# Bootselector_SMD.net
KiCad netlist of a schematic drawn in EAGLE
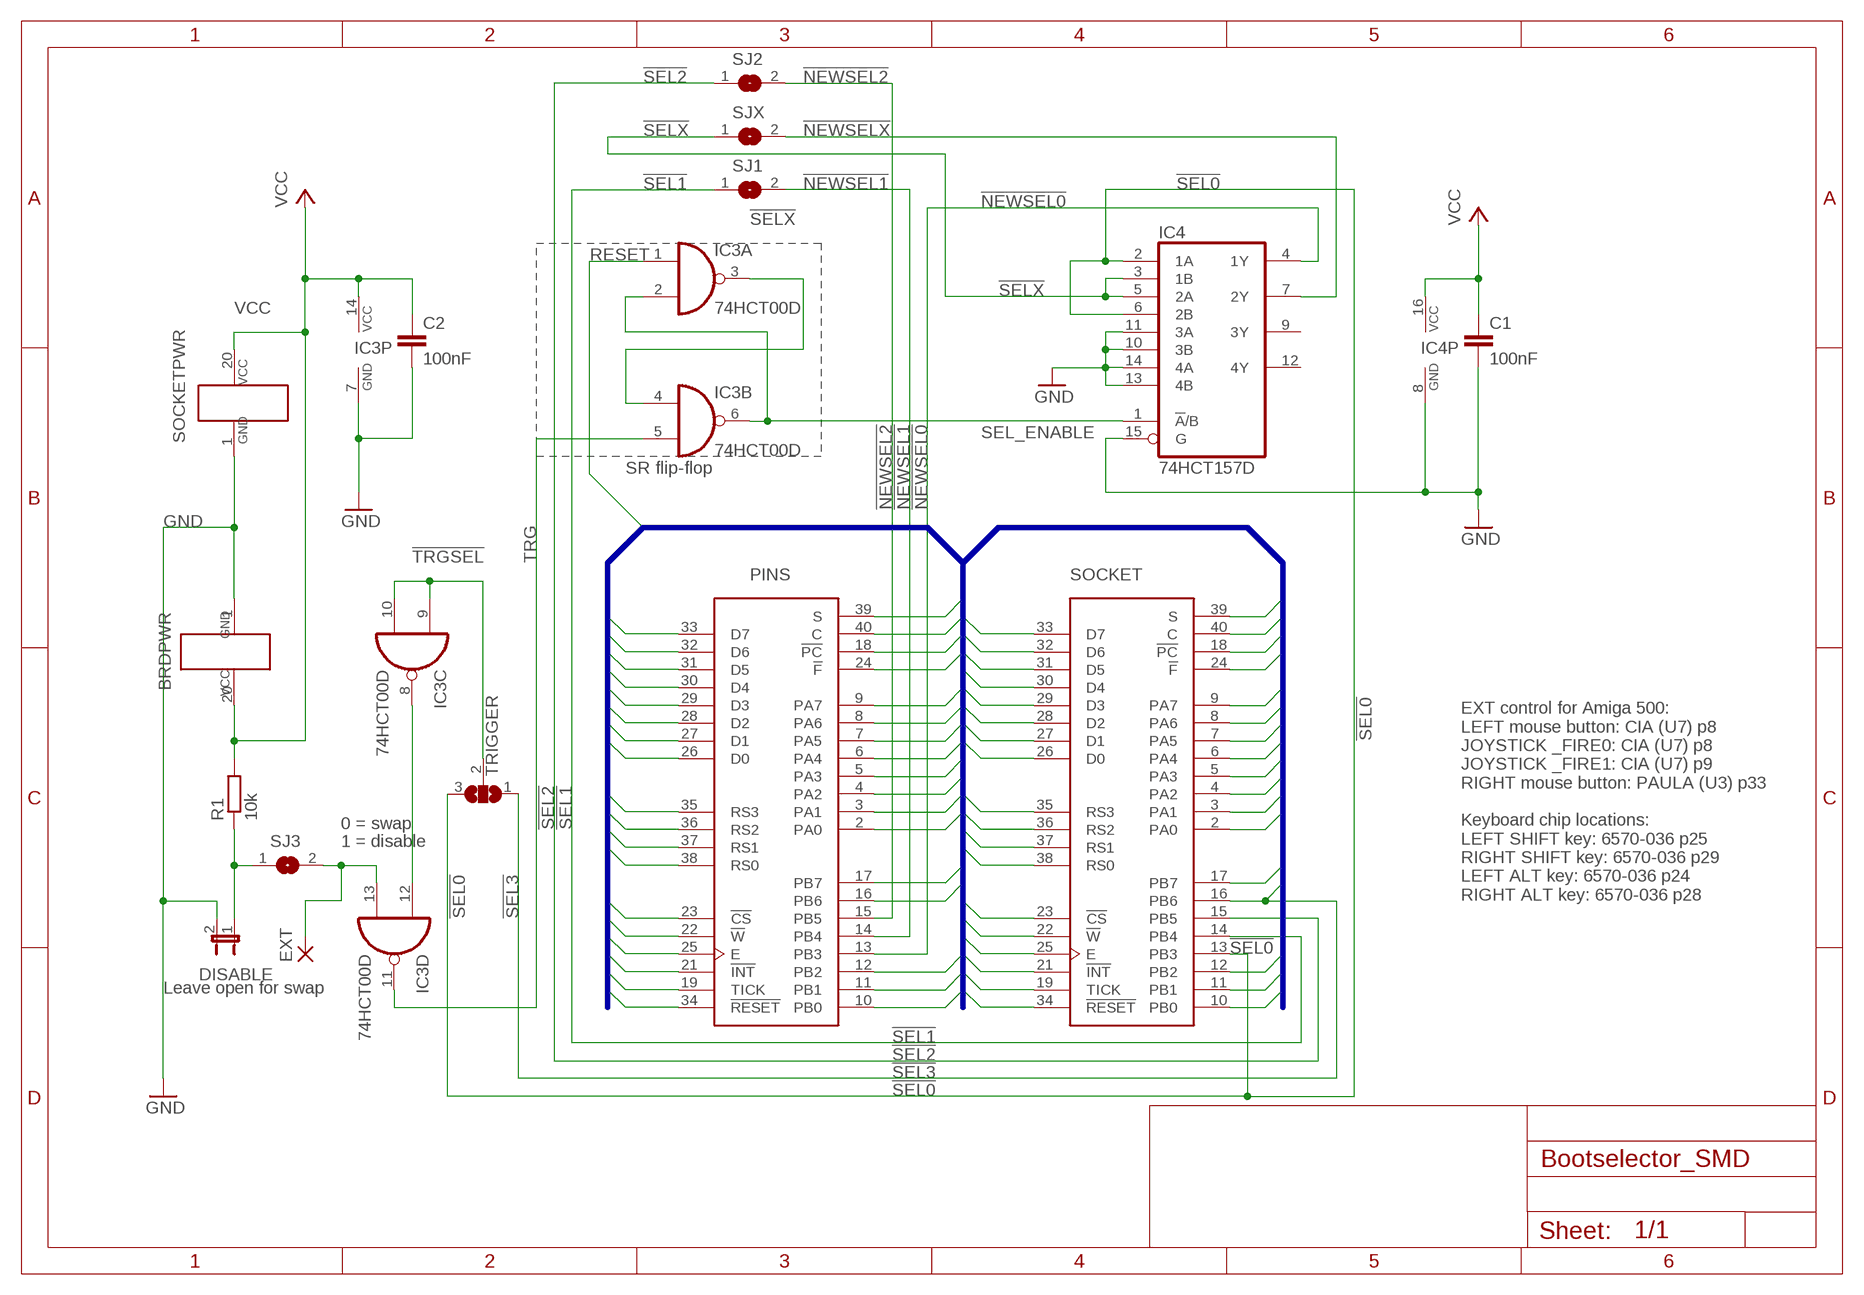
[diagram p0: schematic, sheet 1]

(export (version "E")
  (design (tool "Eeschema 10.0.6"))
  (components
    (comp (ref "BRD")
      (value "PINS")
      (footprint "eagle-import:DIP40-6")
      (libsource (lib "eagle-import") (part "CIA_DIP"))
    )
    (comp (ref "C1")
      (value "100nF")
      (footprint "eagle-import:C0805")
      (libsource (lib "eagle-import") (part "C-EUC0805"))
    )
    (comp (ref "C2")
      (value "100nF")
      (footprint "eagle-import:C0805K")
      (libsource (lib "eagle-import") (part "C-EUC0805K"))
    )
    (comp (ref "DISABLE")
      (value "Leave open for swap")
      (footprint "eagle-import:JP1")
      (libsource (lib "eagle-import") (part "JP1E"))
    )
    (comp (ref "EXT")
      (value "SMD2")
      (footprint "eagle-import:SMD1,27-2,54")
      (libsource (lib "eagle-import") (part "SMD2"))
    )
    (comp (ref "IC3")
      (value "74HCT00D")
      (footprint "eagle-import:SO14")
      (libsource (lib "eagle-import") (part "7400DHCT"))
    )
    (comp (ref "IC4")
      (value "74HCT157D")
      (footprint "eagle-import:SO16")
      (libsource (lib "eagle-import") (part "74157DHCT"))
    )
    (comp (ref "R1")
      (value "10k")
      (footprint "eagle-import:R0805")
      (libsource (lib "eagle-import") (part "R-EU_R0805"))
    )
    (comp (ref "SJ1") (value "SJ") (footprint "eagle-import:SJ") (libsource (lib "eagle-import") (part "SJ")))
    (comp (ref "SJ2") (value "SJ") (footprint "eagle-import:SJ") (libsource (lib "eagle-import") (part "SJ")))
    (comp (ref "SJ3") (value "SJ") (footprint "eagle-import:SJ") (libsource (lib "eagle-import") (part "SJ")))
    (comp (ref "SJX") (value "SJ") (footprint "eagle-import:SJ") (libsource (lib "eagle-import") (part "SJ")))
    (comp (ref "SOCKET")
      (value "CIA_DIP")
      (footprint "eagle-import:DIP40-6")
      (libsource (lib "eagle-import") (part "CIA_DIP"))
    )
    (comp (ref "TRIGGER")
      (value "SJ2W")
      (footprint "eagle-import:SJ_2")
      (libsource (lib "eagle-import") (part "SJ2W"))
    )
  )
  (nets
    (net (code "1") (name "/C") (class "Default")
      (node (ref "BRD") (pin "40") (pinfunction "C_40") (pintype "bidirectional"))
      (node (ref "SOCKET") (pin "40") (pinfunction "C_40") (pintype "bidirectional"))
    )
    (net (code "2") (name "/CS") (class "Default")
      (node (ref "BRD") (pin "23") (pinfunction "~{CS}_23") (pintype "input"))
      (node (ref "SOCKET") (pin "23") (pinfunction "~{CS}_23") (pintype "input"))
    )
    (net (code "3") (name "/D0") (class "Default")
      (node (ref "BRD") (pin "26") (pinfunction "D0_26") (pintype "bidirectional"))
      (node (ref "SOCKET") (pin "26") (pinfunction "D0_26") (pintype "bidirectional"))
    )
    (net (code "4") (name "/D1") (class "Default")
      (node (ref "BRD") (pin "27") (pinfunction "D1_27") (pintype "bidirectional"))
      (node (ref "SOCKET") (pin "27") (pinfunction "D1_27") (pintype "bidirectional"))
    )
    (net (code "5") (name "/D2") (class "Default")
      (node (ref "BRD") (pin "28") (pinfunction "D2_28") (pintype "bidirectional"))
      (node (ref "SOCKET") (pin "28") (pinfunction "D2_28") (pintype "bidirectional"))
    )
    (net (code "6") (name "/D3") (class "Default")
      (node (ref "BRD") (pin "29") (pinfunction "D3_29") (pintype "bidirectional"))
      (node (ref "SOCKET") (pin "29") (pinfunction "D3_29") (pintype "bidirectional"))
    )
    (net (code "7") (name "/D4") (class "Default")
      (node (ref "BRD") (pin "30") (pinfunction "D4_30") (pintype "bidirectional"))
      (node (ref "SOCKET") (pin "30") (pinfunction "D4_30") (pintype "bidirectional"))
    )
    (net (code "8") (name "/D5") (class "Default")
      (node (ref "BRD") (pin "31") (pinfunction "D5_31") (pintype "bidirectional"))
      (node (ref "SOCKET") (pin "31") (pinfunction "D5_31") (pintype "bidirectional"))
    )
    (net (code "9") (name "/D6") (class "Default")
      (node (ref "BRD") (pin "32") (pinfunction "D6_32") (pintype "bidirectional"))
      (node (ref "SOCKET") (pin "32") (pinfunction "D6_32") (pintype "bidirectional"))
    )
    (net (code "10") (name "/D7") (class "Default")
      (node (ref "BRD") (pin "33") (pinfunction "D7_33") (pintype "bidirectional"))
      (node (ref "SOCKET") (pin "33") (pinfunction "D7_33") (pintype "bidirectional"))
    )
    (net (code "11") (name "/E") (class "Default")
      (node (ref "BRD") (pin "25") (pinfunction "E_25") (pintype "input"))
      (node (ref "SOCKET") (pin "25") (pinfunction "E_25") (pintype "input"))
    )
    (net (code "12") (name "/F") (class "Default")
      (node (ref "BRD") (pin "24") (pinfunction "~{F}_24") (pintype "bidirectional"))
      (node (ref "SOCKET") (pin "24") (pinfunction "~{F}_24") (pintype "bidirectional"))
    )
    (net (code "13") (name "/INT") (class "Default")
      (node (ref "BRD") (pin "21") (pinfunction "~{INT}_21") (pintype "output"))
      (node (ref "SOCKET") (pin "21") (pinfunction "~{INT}_21") (pintype "output"))
    )
    (net (code "14") (name "/PA0") (class "Default")
      (node (ref "BRD") (pin "2") (pinfunction "PA0_2") (pintype "bidirectional"))
      (node (ref "SOCKET") (pin "2") (pinfunction "PA0_2") (pintype "bidirectional"))
    )
    (net (code "15") (name "/PA1") (class "Default")
      (node (ref "BRD") (pin "3") (pinfunction "PA1_3") (pintype "bidirectional"))
      (node (ref "SOCKET") (pin "3") (pinfunction "PA1_3") (pintype "bidirectional"))
    )
    (net (code "16") (name "/PA2") (class "Default")
      (node (ref "BRD") (pin "4") (pinfunction "PA2_4") (pintype "bidirectional"))
      (node (ref "SOCKET") (pin "4") (pinfunction "PA2_4") (pintype "bidirectional"))
    )
    (net (code "17") (name "/PA3") (class "Default")
      (node (ref "BRD") (pin "5") (pinfunction "PA3_5") (pintype "bidirectional"))
      (node (ref "SOCKET") (pin "5") (pinfunction "PA3_5") (pintype "bidirectional"))
    )
    (net (code "18") (name "/PA4") (class "Default")
      (node (ref "BRD") (pin "6") (pinfunction "PA4_6") (pintype "bidirectional"))
      (node (ref "SOCKET") (pin "6") (pinfunction "PA4_6") (pintype "bidirectional"))
    )
    (net (code "19") (name "/PA5") (class "Default")
      (node (ref "BRD") (pin "7") (pinfunction "PA5_7") (pintype "bidirectional"))
      (node (ref "SOCKET") (pin "7") (pinfunction "PA5_7") (pintype "bidirectional"))
    )
    (net (code "20") (name "/PA6") (class "Default")
      (node (ref "BRD") (pin "8") (pinfunction "PA6_8") (pintype "bidirectional"))
      (node (ref "SOCKET") (pin "8") (pinfunction "PA6_8") (pintype "bidirectional"))
    )
    (net (code "21") (name "/PA7") (class "Default")
      (node (ref "BRD") (pin "9") (pinfunction "PA7_9") (pintype "bidirectional"))
      (node (ref "SOCKET") (pin "9") (pinfunction "PA7_9") (pintype "bidirectional"))
    )
    (net (code "22") (name "/PB0") (class "Default")
      (node (ref "BRD") (pin "10") (pinfunction "PB0_10") (pintype "bidirectional"))
      (node (ref "SOCKET") (pin "10") (pinfunction "PB0_10") (pintype "bidirectional"))
    )
    (net (code "23") (name "/PB1") (class "Default")
      (node (ref "BRD") (pin "11") (pinfunction "PB1_11") (pintype "bidirectional"))
      (node (ref "SOCKET") (pin "11") (pinfunction "PB1_11") (pintype "bidirectional"))
    )
    (net (code "24") (name "/PB2") (class "Default")
      (node (ref "BRD") (pin "12") (pinfunction "PB2_12") (pintype "bidirectional"))
      (node (ref "SOCKET") (pin "12") (pinfunction "PB2_12") (pintype "bidirectional"))
    )
    (net (code "25") (name "/PB7") (class "Default")
      (node (ref "BRD") (pin "17") (pinfunction "PB7_17") (pintype "bidirectional"))
      (node (ref "SOCKET") (pin "17") (pinfunction "PB7_17") (pintype "bidirectional"))
    )
    (net (code "26") (name "/PC") (class "Default")
      (node (ref "BRD") (pin "18") (pinfunction "~{PC}_18") (pintype "bidirectional"))
      (node (ref "SOCKET") (pin "18") (pinfunction "~{PC}_18") (pintype "bidirectional"))
    )
    (net (code "27") (name "/RESET") (class "Default")
      (node (ref "BRD") (pin "34") (pinfunction "~{RESET}_34") (pintype "input"))
      (node (ref "IC3") (pin "1") (pinfunction "I0_1") (pintype "input"))
      (node (ref "SOCKET") (pin "34") (pinfunction "~{RESET}_34") (pintype "input"))
    )
    (net (code "28") (name "/RS0") (class "Default")
      (node (ref "BRD") (pin "38") (pinfunction "RS0_38") (pintype "input"))
      (node (ref "SOCKET") (pin "38") (pinfunction "RS0_38") (pintype "input"))
    )
    (net (code "29") (name "/RS1") (class "Default")
      (node (ref "BRD") (pin "37") (pinfunction "RS1_37") (pintype "input"))
      (node (ref "SOCKET") (pin "37") (pinfunction "RS1_37") (pintype "input"))
    )
    (net (code "30") (name "/RS2") (class "Default")
      (node (ref "BRD") (pin "36") (pinfunction "RS2_36") (pintype "input"))
      (node (ref "SOCKET") (pin "36") (pinfunction "RS2_36") (pintype "input"))
    )
    (net (code "31") (name "/RS3") (class "Default")
      (node (ref "BRD") (pin "35") (pinfunction "RS3_35") (pintype "input"))
      (node (ref "SOCKET") (pin "35") (pinfunction "RS3_35") (pintype "input"))
    )
    (net (code "32") (name "/S") (class "Default")
      (node (ref "BRD") (pin "39") (pinfunction "S_39") (pintype "bidirectional"))
      (node (ref "SOCKET") (pin "39") (pinfunction "S_39") (pintype "bidirectional"))
    )
    (net (code "33") (name "/SEL_ENABLE") (class "Default")
      (node (ref "IC3") (pin "2") (pinfunction "I1_2") (pintype "input"))
      (node (ref "IC3") (pin "6") (pinfunction "O_6") (pintype "output"))
      (node (ref "IC4") (pin "1") (pinfunction "~{A}/B_1") (pintype "input"))
    )
    (net (code "34") (name "/TICK") (class "Default")
      (node (ref "BRD") (pin "19") (pinfunction "TICK_19") (pintype "input"))
      (node (ref "SOCKET") (pin "19") (pinfunction "TICK_19") (pintype "input"))
    )
    (net (code "35") (name "/TRG") (class "Default")
      (node (ref "IC3") (pin "11") (pinfunction "O_11") (pintype "output"))
      (node (ref "IC3") (pin "5") (pinfunction "I1_5") (pintype "input"))
    )
    (net (code "36") (name "/W") (class "Default")
      (node (ref "BRD") (pin "22") (pinfunction "~{W}_22") (pintype "input"))
      (node (ref "SOCKET") (pin "22") (pinfunction "~{W}_22") (pintype "input"))
    )
    (net (code "37") (name "/~{NEWSEL0}") (class "Default")
      (node (ref "BRD") (pin "13") (pinfunction "PB3_13") (pintype "bidirectional"))
      (node (ref "IC4") (pin "4") (pinfunction "1Y_4") (pintype "output"))
    )
    (net (code "38") (name "/~{NEWSEL1}") (class "Default")
      (node (ref "BRD") (pin "14") (pinfunction "PB4_14") (pintype "bidirectional"))
      (node (ref "SJ1") (pin "2") (pinfunction "2_2") (pintype "passive"))
    )
    (net (code "39") (name "/~{NEWSEL2}") (class "Default")
      (node (ref "BRD") (pin "15") (pinfunction "PB5_15") (pintype "bidirectional"))
      (node (ref "SJ2") (pin "2") (pinfunction "2_2") (pintype "passive"))
    )
    (net (code "40") (name "/~{NEWSELX}") (class "Default")
      (node (ref "IC4") (pin "7") (pinfunction "2Y_7") (pintype "output"))
      (node (ref "SJX") (pin "2") (pinfunction "2_2") (pintype "passive"))
    )
    (net (code "41") (name "/~{SEL0}") (class "Default")
      (node (ref "IC4") (pin "2") (pinfunction "1A_2") (pintype "input"))
      (node (ref "IC4") (pin "6") (pinfunction "2B_6") (pintype "input"))
      (node (ref "SOCKET") (pin "13") (pinfunction "PB3_13") (pintype "bidirectional"))
      (node (ref "TRIGGER") (pin "3") (pinfunction "3_3") (pintype "passive"))
    )
    (net (code "42") (name "/~{SEL1}") (class "Default")
      (node (ref "SJ1") (pin "1") (pinfunction "1_1") (pintype "passive"))
      (node (ref "SOCKET") (pin "14") (pinfunction "PB4_14") (pintype "bidirectional"))
    )
    (net (code "43") (name "/~{SEL2}") (class "Default")
      (node (ref "SJ2") (pin "1") (pinfunction "1_1") (pintype "passive"))
      (node (ref "SOCKET") (pin "15") (pinfunction "PB5_15") (pintype "bidirectional"))
    )
    (net (code "44") (name "/~{SEL3}") (class "Default")
      (node (ref "BRD") (pin "16") (pinfunction "PB6_16") (pintype "bidirectional"))
      (node (ref "SOCKET") (pin "16") (pinfunction "PB6_16") (pintype "bidirectional"))
      (node (ref "TRIGGER") (pin "1") (pinfunction "1_1") (pintype "passive"))
    )
    (net (code "45") (name "/~{SELX}") (class "Default")
      (node (ref "IC4") (pin "3") (pinfunction "1B_3") (pintype "input"))
      (node (ref "IC4") (pin "5") (pinfunction "2A_5") (pintype "input"))
      (node (ref "SJX") (pin "1") (pinfunction "1_1") (pintype "passive"))
    )
    (net (code "46") (name "/~{TRGSEL}") (class "Default")
      (node (ref "IC3") (pin "10") (pinfunction "I1_10") (pintype "input"))
      (node (ref "IC3") (pin "9") (pinfunction "I0_9") (pintype "input"))
      (node (ref "TRIGGER") (pin "2") (pinfunction "2_2") (pintype "passive"))
    )
    (net (code "47") (name "GND") (class "Default")
      (node (ref "BRD") (pin "1") (pinfunction "GND1_1") (pintype "power_in"))
      (node (ref "C1") (pin "2") (pinfunction "2_2") (pintype "passive"))
      (node (ref "C2") (pin "2") (pinfunction "2_2") (pintype "passive"))
      (node (ref "DISABLE") (pin "2") (pinfunction "2_2") (pintype "passive"))
      (node (ref "IC3") (pin "7") (pinfunction "GND_7") (pintype "power_in"))
      (node (ref "IC4") (pin "10") (pinfunction "3B_10") (pintype "input"))
      (node (ref "IC4") (pin "11") (pinfunction "3A_11") (pintype "input"))
      (node (ref "IC4") (pin "13") (pinfunction "4B_13") (pintype "input"))
      (node (ref "IC4") (pin "14") (pinfunction "4A_14") (pintype "input"))
      (node (ref "IC4") (pin "15") (pinfunction "G_15") (pintype "input"))
      (node (ref "IC4") (pin "8") (pinfunction "GND_8") (pintype "power_in"))
      (node (ref "SOCKET") (pin "1") (pinfunction "GND1_1") (pintype "power_in"))
    )
    (net (code "48") (name "Net-(DISABLE-Pad1)") (class "Default")
      (node (ref "DISABLE") (pin "1") (pinfunction "1_1") (pintype "passive"))
      (node (ref "R1") (pin "1") (pinfunction "1_1") (pintype "passive"))
      (node (ref "SJ3") (pin "1") (pinfunction "1_1") (pintype "passive"))
    )
    (net (code "49") (name "Net-(EXT-P)") (class "Default")
      (node (ref "EXT") (pin "1") (pinfunction "P_1") (pintype "passive"))
      (node (ref "IC3") (pin "13") (pinfunction "I1_13") (pintype "input"))
      (node (ref "SJ3") (pin "2") (pinfunction "2_2") (pintype "passive"))
    )
    (net (code "50") (name "Net-(IC3A-O)") (class "Default")
      (node (ref "IC3") (pin "3") (pinfunction "O_3") (pintype "output"))
      (node (ref "IC3") (pin "4") (pinfunction "I0_4") (pintype "input"))
    )
    (net (code "51") (name "Net-(IC3C-O)") (class "Default")
      (node (ref "IC3") (pin "12") (pinfunction "I0_12") (pintype "input"))
      (node (ref "IC3") (pin "8") (pinfunction "O_8") (pintype "output"))
    )
    (net (code "52") (name "VCC") (class "Default")
      (node (ref "BRD") (pin "20") (pinfunction "VCC1_20") (pintype "power_in"))
      (node (ref "C1") (pin "1") (pinfunction "1_1") (pintype "passive"))
      (node (ref "C2") (pin "1") (pinfunction "1_1") (pintype "passive"))
      (node (ref "IC3") (pin "14") (pinfunction "VCC_14") (pintype "power_in"))
      (node (ref "IC4") (pin "16") (pinfunction "VCC_16") (pintype "power_in"))
      (node (ref "R1") (pin "2") (pinfunction "2_2") (pintype "passive"))
      (node (ref "SOCKET") (pin "20") (pinfunction "VCC1_20") (pintype "power_in"))
    )
    (net (code "53") (name "unconnected-(IC4A-3Y-Pad9)") (class "Default")
      (node (ref "IC4") (pin "9") (pinfunction "3Y_9") (pintype "output"))
    )
    (net (code "54") (name "unconnected-(IC4A-4Y-Pad12)") (class "Default")
      (node (ref "IC4") (pin "12") (pinfunction "4Y_12") (pintype "output"))
    )
  )
)
